# ArduinoSmarticleNoAccelNoSolar.net
KiCad netlist of a schematic drawn in EAGLE
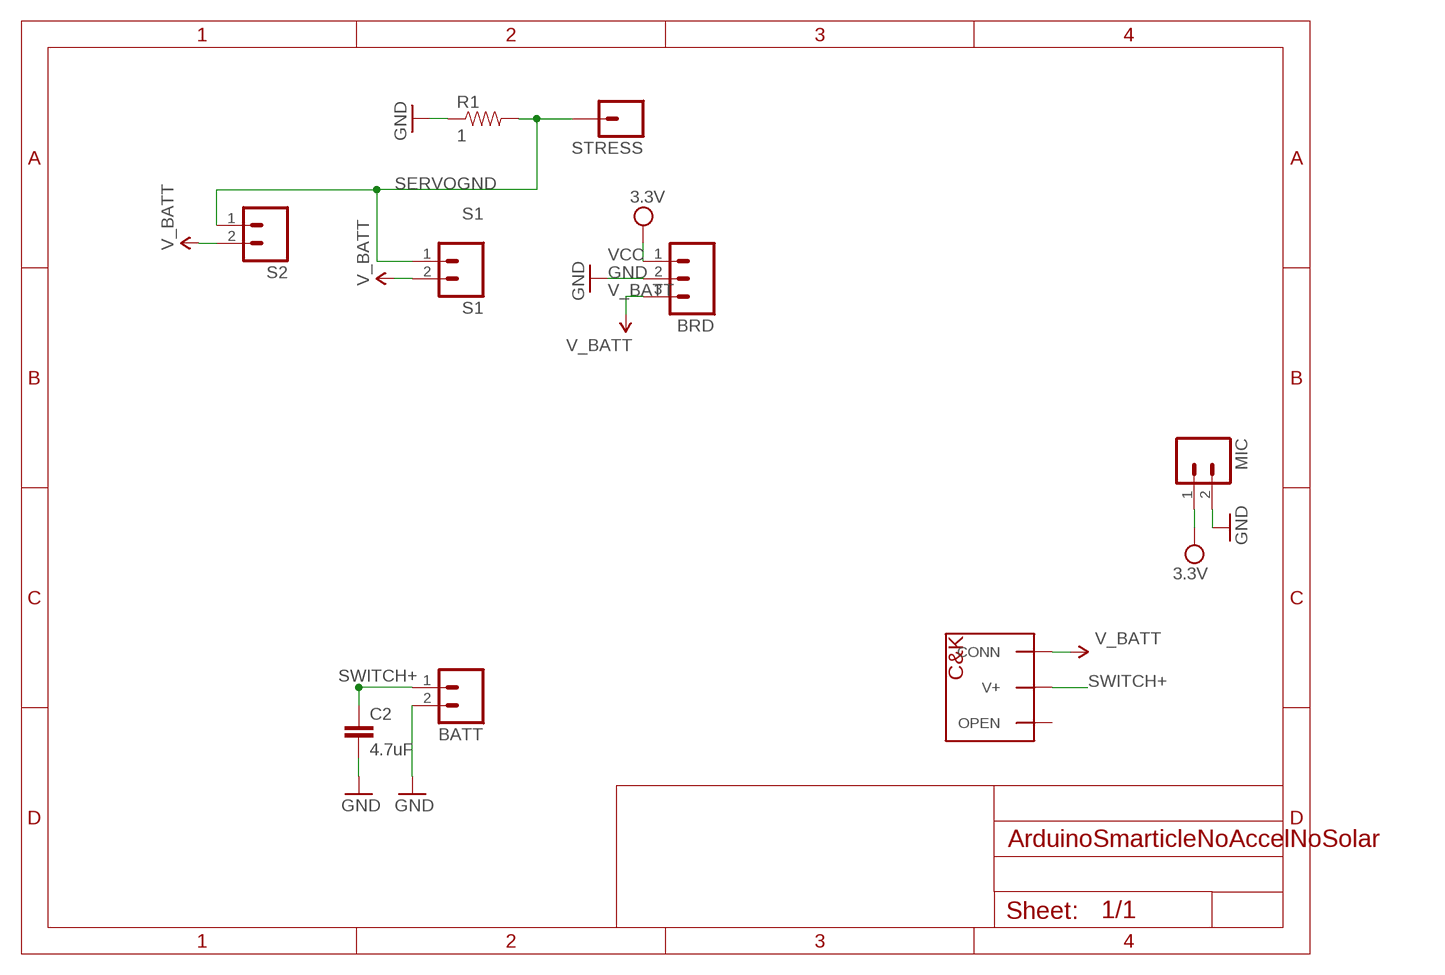
[diagram p0: schematic, sheet 1]

(export (version "E")
  (design (tool "Eeschema 10.0.6"))
  (components
    (comp (ref "BATT")
      (value "M02PTH")
      (footprint "eagle-import:1X02")
      (libsource (lib "eagle-import") (part "M02PTH"))
    )
    (comp (ref "BRD")
      (value "M03PTH")
      (footprint "eagle-import:1X03")
      (libsource (lib "eagle-import") (part "M03PTH"))
    )
    (comp (ref "C2")
      (value "4.7uF")
      (footprint "eagle-import:0603-CAP")
      (libsource (lib "eagle-import") (part "4.7UF-6.3V-10%(0603)0603"))
    )
    (comp (ref "MIC")
      (value "M02PTH")
      (footprint "eagle-import:1X02")
      (libsource (lib "eagle-import") (part "M02PTH"))
    )
    (comp (ref "R1")
      (value "1")
      (footprint "eagle-import:0603-RES")
      (libsource (lib "eagle-import") (part "2.0KOHM1/10W5%(0603)"))
    )
    (comp (ref "S1")
      (value "S1")
      (footprint "eagle-import:1X02")
      (libsource (lib "eagle-import") (part "M02PTH"))
    )
    (comp (ref "S2")
      (value "M02PTH")
      (footprint "eagle-import:1X02")
      (libsource (lib "eagle-import") (part "M02PTH"))
    )
    (comp (ref "STRESS")
      (value "M01PTH")
      (footprint "eagle-import:1X01")
      (libsource (lib "eagle-import") (part "M01PTH"))
    )
    (comp (ref "U$1")
      (value "WILL-BLACKSLIDESWITCH")
      (footprint "eagle-import:WILL-BLACKSLIDESWITCH")
      (libsource (lib "eagle-import") (part "WILL-BLACKSLIDESWITCH"))
    )
  )
  (nets
    (net (code "1") (name "/SERVOGND") (class "Default")
      (node (ref "R1") (pin "2") (pinfunction "2_2") (pintype "passive"))
      (node (ref "S1") (pin "1") (pinfunction "1_1") (pintype "passive"))
      (node (ref "S2") (pin "1") (pinfunction "1_1") (pintype "passive"))
      (node (ref "STRESS") (pin "1") (pinfunction "1_1") (pintype "passive"))
    )
    (net (code "2") (name "/SWITCH+") (class "Default")
      (node (ref "BATT") (pin "1") (pinfunction "1_1") (pintype "passive"))
      (node (ref "C2") (pin "1") (pinfunction "1_1") (pintype "passive"))
      (node (ref "U$1") (pin "V+") (pinfunction "V+_V+") (pintype "bidirectional"))
    )
    (net (code "3") (name "3.3V") (class "Default")
      (node (ref "BRD") (pin "1") (pinfunction "1_1") (pintype "passive"))
      (node (ref "MIC") (pin "1") (pinfunction "1_1") (pintype "passive"))
    )
    (net (code "4") (name "GND") (class "Default")
      (node (ref "BATT") (pin "2") (pinfunction "2_2") (pintype "passive"))
      (node (ref "BRD") (pin "2") (pinfunction "2_2") (pintype "passive"))
      (node (ref "C2") (pin "2") (pinfunction "2_2") (pintype "passive"))
      (node (ref "MIC") (pin "2") (pinfunction "2_2") (pintype "passive"))
      (node (ref "R1") (pin "1") (pinfunction "1_1") (pintype "passive"))
    )
    (net (code "5") (name "V_BATT") (class "Default")
      (node (ref "BRD") (pin "3") (pinfunction "3_3") (pintype "passive"))
      (node (ref "S1") (pin "2") (pinfunction "2_2") (pintype "passive"))
      (node (ref "S2") (pin "2") (pinfunction "2_2") (pintype "passive"))
      (node (ref "U$1") (pin "CONN") (pinfunction "CONN_CONN") (pintype "bidirectional"))
    )
    (net (code "6") (name "unconnected-(U$1-OPEN-PadNC)") (class "Default")
      (node (ref "U$1") (pin "NC") (pinfunction "OPEN_NC") (pintype "bidirectional"))
    )
  )
)
